# Sheet1.net
KiCad netlist of a schematic drawn in Altium Designer
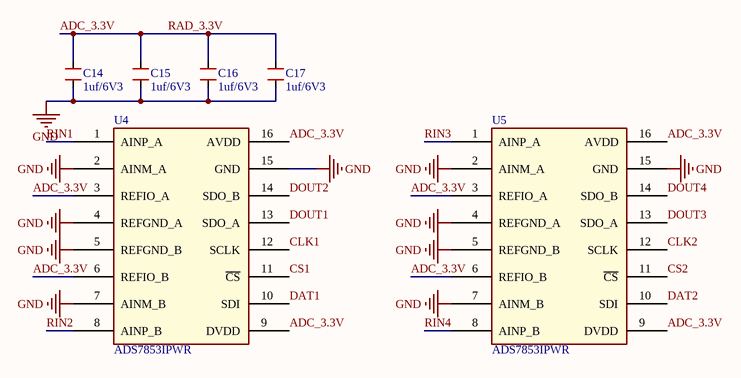
[diagram p0: Sheet1.SchDoc]

(export (version "E")
  (design (tool "Eeschema 10.0.6"))
  (components
    (comp (ref "C14")
      (value "1uf/6V3")
      (footprint "CAP0603")
      (description "Generic Capacitor")
      (libsource (lib "MZ7XB_Fun") (part "CAPACITOR_1UF"))
    )
    (comp (ref "C15")
      (value "1uf/6V3")
      (footprint "CAP0603")
      (description "Generic Capacitor")
      (libsource (lib "MZ7XB_Fun") (part "CAPACITOR_1UF"))
    )
    (comp (ref "C16")
      (value "1uf/6V3")
      (footprint "CAP0603")
      (description "Generic Capacitor")
      (libsource (lib "MZ7XB_Fun") (part "CAPACITOR_1UF"))
    )
    (comp (ref "C17")
      (value "1uf/6V3")
      (footprint "CAP0603")
      (description "Generic Capacitor")
      (libsource (lib "MZ7XB_Fun") (part "CAPACITOR_1UF"))
    )
    (comp (ref "U4")
      (value "ADS7853IPWR")
      (footprint "TSSOP16-0.65-5X4.4MM")
      (libsource (lib "MZ7XB_Fun") (part "ADS7853IPWR"))
    )
    (comp (ref "U5")
      (value "ADS7853IPWR")
      (footprint "TSSOP16-0.65-5X4.4MM")
      (libsource (lib "MZ7XB_Fun") (part "ADS7853IPWR"))
    )
  )
  (nets
    (net (code "1") (name "/ADC_3.3V") (class "Default")
      (node (ref "C14") (pin "1") (pinfunction "1_1") (pintype "passive"))
      (node (ref "C15") (pin "1") (pinfunction "1_1") (pintype "passive"))
      (node (ref "C16") (pin "1") (pinfunction "1_1") (pintype "passive"))
      (node (ref "C17") (pin "1") (pinfunction "1_1") (pintype "passive"))
      (node (ref "U4") (pin "16") (pinfunction "AVDD_16") (pintype "passive"))
      (node (ref "U4") (pin "3") (pinfunction "REFIO_A_3") (pintype "passive"))
      (node (ref "U4") (pin "6") (pinfunction "REFIO_B_6") (pintype "passive"))
      (node (ref "U4") (pin "9") (pinfunction "DVDD_9") (pintype "passive"))
      (node (ref "U5") (pin "16") (pinfunction "AVDD_16") (pintype "passive"))
      (node (ref "U5") (pin "3") (pinfunction "REFIO_A_3") (pintype "passive"))
      (node (ref "U5") (pin "6") (pinfunction "REFIO_B_6") (pintype "passive"))
      (node (ref "U5") (pin "9") (pinfunction "DVDD_9") (pintype "passive"))
    )
    (net (code "2") (name "/CLK1") (class "Default")
      (node (ref "U4") (pin "12") (pinfunction "SCLK_12") (pintype "passive"))
    )
    (net (code "3") (name "/CLK2") (class "Default")
      (node (ref "U5") (pin "12") (pinfunction "SCLK_12") (pintype "passive"))
    )
    (net (code "4") (name "/CS1") (class "Default")
      (node (ref "U4") (pin "11") (pinfunction "~{CS}_11") (pintype "passive"))
    )
    (net (code "5") (name "/CS2") (class "Default")
      (node (ref "U5") (pin "11") (pinfunction "~{CS}_11") (pintype "passive"))
    )
    (net (code "6") (name "/DAT1") (class "Default")
      (node (ref "U4") (pin "10") (pinfunction "SDI_10") (pintype "passive"))
    )
    (net (code "7") (name "/DAT2") (class "Default")
      (node (ref "U5") (pin "10") (pinfunction "SDI_10") (pintype "passive"))
    )
    (net (code "8") (name "/DOUT1") (class "Default")
      (node (ref "U4") (pin "13") (pinfunction "SDO_A_13") (pintype "passive"))
    )
    (net (code "9") (name "/DOUT2") (class "Default")
      (node (ref "U4") (pin "14") (pinfunction "SDO_B_14") (pintype "passive"))
    )
    (net (code "10") (name "/DOUT3") (class "Default")
      (node (ref "U5") (pin "13") (pinfunction "SDO_A_13") (pintype "passive"))
    )
    (net (code "11") (name "/DOUT4") (class "Default")
      (node (ref "U5") (pin "14") (pinfunction "SDO_B_14") (pintype "passive"))
    )
    (net (code "12") (name "/RIN1") (class "Default")
      (node (ref "U4") (pin "1") (pinfunction "AINP_A_1") (pintype "passive"))
    )
    (net (code "13") (name "/RIN2") (class "Default")
      (node (ref "U4") (pin "8") (pinfunction "AINP_B_8") (pintype "passive"))
    )
    (net (code "14") (name "/RIN3") (class "Default")
      (node (ref "U5") (pin "1") (pinfunction "AINP_A_1") (pintype "passive"))
    )
    (net (code "15") (name "/RIN4") (class "Default")
      (node (ref "U5") (pin "8") (pinfunction "AINP_B_8") (pintype "passive"))
    )
    (net (code "16") (name "GND") (class "Default")
      (node (ref "C14") (pin "2") (pinfunction "2_2") (pintype "passive"))
      (node (ref "C15") (pin "2") (pinfunction "2_2") (pintype "passive"))
      (node (ref "C16") (pin "2") (pinfunction "2_2") (pintype "passive"))
      (node (ref "C17") (pin "2") (pinfunction "2_2") (pintype "passive"))
      (node (ref "U4") (pin "15") (pinfunction "GND_15") (pintype "passive"))
      (node (ref "U4") (pin "2") (pinfunction "AINM_A_2") (pintype "passive"))
      (node (ref "U4") (pin "4") (pinfunction "REFGND_A_4") (pintype "passive"))
      (node (ref "U4") (pin "5") (pinfunction "REFGND_B_5") (pintype "passive"))
      (node (ref "U4") (pin "7") (pinfunction "AINM_B_7") (pintype "passive"))
      (node (ref "U5") (pin "15") (pinfunction "GND_15") (pintype "passive"))
      (node (ref "U5") (pin "2") (pinfunction "AINM_A_2") (pintype "passive"))
      (node (ref "U5") (pin "4") (pinfunction "REFGND_A_4") (pintype "passive"))
      (node (ref "U5") (pin "5") (pinfunction "REFGND_B_5") (pintype "passive"))
      (node (ref "U5") (pin "7") (pinfunction "AINM_B_7") (pintype "passive"))
    )
  )
)
